# Circuits_task.net
KiCad netlist of a schematic drawn in Altium Designer
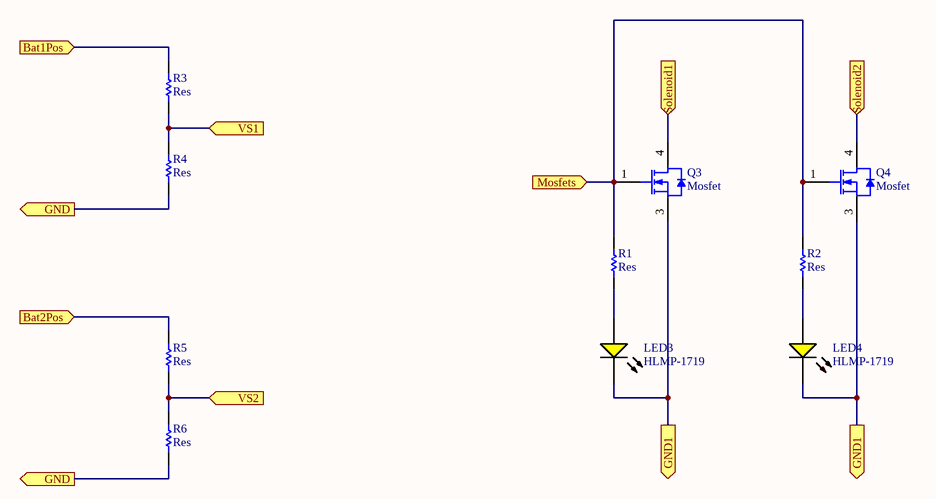
[diagram p0: Circuits_task.SchDoc]

(export (version "E")
  (design (tool "Eeschema 10.0.6"))
  (components
    (comp (ref "LED3")
      (value "HLMP-1719")
      (footprint "AVAG-HLMP-1719_V")
      (description "Low Current LED Lamp, T-1 (3 mm), 1.8 V, 2 mA, -40 to 100 degC, 2-Pin THD, RoHS, Bulk")
      (fields (field (name "MANUFACTURER") "AvagoTechnologies"))
      (libsource (lib "Altium Content Vault") (part "LED-YELLOW-AK-2"))
    )
    (comp (ref "LED4")
      (value "HLMP-1719")
      (footprint "AVAG-HLMP-1719_V")
      (description "Low Current LED Lamp, T-1 (3 mm), 1.8 V, 2 mA, -40 to 100 degC, 2-Pin THD, RoHS, Bulk")
      (fields (field (name "MANUFACTURER") "AvagoTechnologies"))
      (libsource (lib "Altium Content Vault") (part "LED-YELLOW-AK-2"))
    )
    (comp (ref "Q3")
      (value "Mosfet")
      (footprint "ONSC-DPAK-3-369AA-01_V")
      (description "Power MOSFET, 25 V, 65 A, Single N-Channel, 3-Pin DPAK, Pb-Free, Tape and Reel")
      (fields (field (name "PARTNUMBER") "NTD4860NT4G") (field (name "MANUFACTURER") "On Semiconductor"))
      (libsource (lib "Altium Content Vault") (part "ONSC-NMOS-G1S3D4-3_B"))
    )
    (comp (ref "Q4")
      (value "Mosfet")
      (footprint "ONSC-DPAK-3-369AA-01_V")
      (description "Power MOSFET, 25 V, 65 A, Single N-Channel, 3-Pin DPAK, Pb-Free, Tape and Reel")
      (fields (field (name "PARTNUMBER") "NTD4860NT4G") (field (name "MANUFACTURER") "On Semiconductor"))
      (libsource (lib "Altium Content Vault") (part "ONSC-NMOS-G1S3D4-3_B"))
    )
    (comp (ref "R1")
      (value "Res")
      (footprint "RESC1005X40X25LL05T10")
      (fields (field (name "MANUFACTURER") "Multicomp") (field (name "PART NUMBER") "MCMR04X1203FTL"))
      (libsource (lib "Altium Content Vault") (part "RES"))
    )
    (comp (ref "R2")
      (value "Res")
      (footprint "RESC1005X40X25LL05T10")
      (fields (field (name "MANUFACTURER") "Multicomp") (field (name "PART NUMBER") "MCMR04X1203FTL"))
      (libsource (lib "Altium Content Vault") (part "RES"))
    )
    (comp (ref "R3")
      (value "Res")
      (footprint "RESC1005X40X25LL05T10")
      (fields (field (name "MANUFACTURER") "Multicomp") (field (name "PART NUMBER") "MCMR04X1203FTL"))
      (libsource (lib "Altium Content Vault") (part "RES"))
    )
    (comp (ref "R4")
      (value "Res")
      (footprint "RESC1005X40X25LL05T10")
      (fields (field (name "MANUFACTURER") "Multicomp") (field (name "PART NUMBER") "MCMR04X1203FTL"))
      (libsource (lib "Altium Content Vault") (part "RES"))
    )
    (comp (ref "R5")
      (value "Res")
      (footprint "RESC1005X40X25LL05T10")
      (fields (field (name "MANUFACTURER") "Multicomp") (field (name "PART NUMBER") "MCMR04X1203FTL"))
      (libsource (lib "Altium Content Vault") (part "RES"))
    )
    (comp (ref "R6")
      (value "Res")
      (footprint "RESC1005X40X25LL05T10")
      (fields (field (name "MANUFACTURER") "Multicomp") (field (name "PART NUMBER") "MCMR04X1203FTL"))
      (libsource (lib "Altium Content Vault") (part "RES"))
    )
  )
  (nets
    (net (code "1") (name "/Bat1Pos") (class "Default")
      (node (ref "R3") (pin "2") (pinfunction "2_2") (pintype "passive"))
    )
    (net (code "2") (name "/Bat2Pos") (class "Default")
      (node (ref "R5") (pin "2") (pinfunction "2_2") (pintype "passive"))
    )
    (net (code "3") (name "/GND") (class "Default")
      (node (ref "R4") (pin "1") (pinfunction "1_1") (pintype "passive"))
      (node (ref "R6") (pin "1") (pinfunction "1_1") (pintype "passive"))
    )
    (net (code "4") (name "/GND1") (class "Default")
      (node (ref "LED3") (pin "2") (pinfunction "K_2") (pintype "passive"))
      (node (ref "LED4") (pin "2") (pinfunction "K_2") (pintype "passive"))
      (node (ref "Q3") (pin "3") (pinfunction "S_3") (pintype "passive"))
      (node (ref "Q4") (pin "3") (pinfunction "S_3") (pintype "passive"))
    )
    (net (code "5") (name "/Mosfets") (class "Default")
      (node (ref "Q3") (pin "1") (pinfunction "G_1") (pintype "passive"))
      (node (ref "Q4") (pin "1") (pinfunction "G_1") (pintype "passive"))
      (node (ref "R1") (pin "2") (pinfunction "2_2") (pintype "passive"))
      (node (ref "R2") (pin "2") (pinfunction "2_2") (pintype "passive"))
    )
    (net (code "6") (name "/Solenoid1") (class "Default")
      (node (ref "Q3") (pin "4") (pinfunction "D_4") (pintype "passive"))
    )
    (net (code "7") (name "/Solenoid2") (class "Default")
      (node (ref "Q4") (pin "4") (pinfunction "D_4") (pintype "passive"))
    )
    (net (code "8") (name "/VS1") (class "Default")
      (node (ref "R3") (pin "1") (pinfunction "1_1") (pintype "passive"))
      (node (ref "R4") (pin "2") (pinfunction "2_2") (pintype "passive"))
    )
    (net (code "9") (name "/VS2") (class "Default")
      (node (ref "R5") (pin "1") (pinfunction "1_1") (pintype "passive"))
      (node (ref "R6") (pin "2") (pinfunction "2_2") (pintype "passive"))
    )
    (net (code "10") (name "Net-(LED3-A)") (class "Default")
      (node (ref "LED3") (pin "1") (pinfunction "A_1") (pintype "passive"))
      (node (ref "R1") (pin "1") (pinfunction "1_1") (pintype "passive"))
    )
    (net (code "11") (name "Net-(LED4-A)") (class "Default")
      (node (ref "LED4") (pin "1") (pinfunction "A_1") (pintype "passive"))
      (node (ref "R2") (pin "1") (pinfunction "1_1") (pintype "passive"))
    )
  )
)
